# DAC.net
KiCad netlist of a schematic drawn in Altium Designer
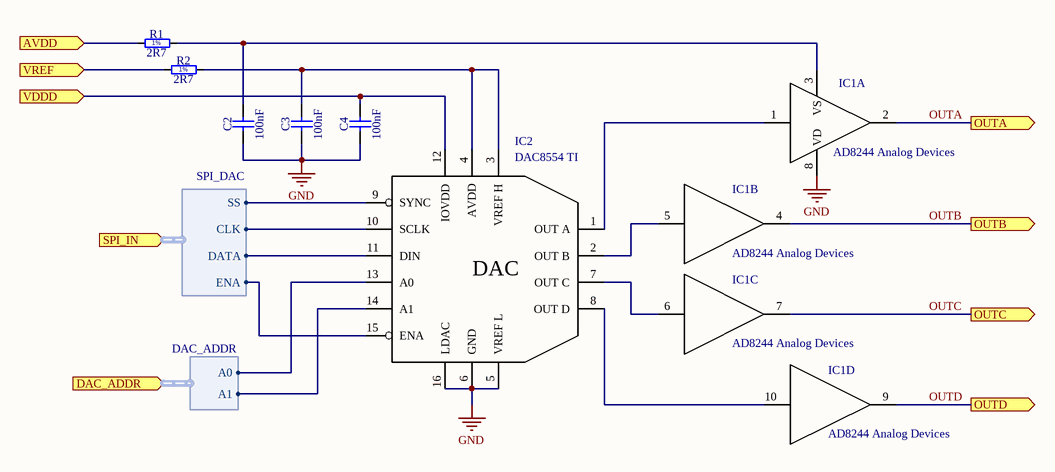
[diagram p0: DAC.SchDoc]

(export (version "E")
  (design (tool "Eeschema 10.0.6"))
  (components
    (comp (ref "C2")
      (value "100nF")
      (footprint "CAPC2012X135N")
      (description "Non-polarised capacitor")
      (fields
        (field (name "PART NUMBER") "CC0805_100NF_50V_10%_X7R")
        (field (name "VOLTAGE") "50V")
        (field (name "AUTHOR") "CERN DEM JLC")
      )
      (libsource (lib "Capacitors") (part "Capacitor - non polarized"))
    )
    (comp (ref "C3")
      (value "100nF")
      (footprint "CAPC2012X135N")
      (description "Non-polarised capacitor")
      (fields
        (field (name "PART NUMBER") "CC0805_100NF_50V_10%_X7R")
        (field (name "VOLTAGE") "50V")
        (field (name "AUTHOR") "CERN DEM JLC")
      )
      (libsource (lib "Capacitors") (part "Capacitor - non polarized"))
    )
    (comp (ref "C4")
      (value "100nF")
      (footprint "CAPC2012X135N")
      (description "Non-polarised capacitor")
      (fields
        (field (name "PART NUMBER") "CC0805_100NF_50V_10%_X7R")
        (field (name "VOLTAGE") "50V")
        (field (name "AUTHOR") "CERN DEM JLC")
      )
      (libsource (lib "Capacitors") (part "Capacitor - non polarized"))
    )
    (comp (ref "IC1")
      (value "AD8244 Analog Devices")
      (footprint "TSSOP50P490X110-10N")
      (fields (field (name "MANUFACTURER") "Analog Devices"))
      (libsource (lib "Additional") (part "AD8244"))
    )
    (comp (ref "IC2")
      (value "DAC8554 TI")
      (footprint "TSOP65P640X120-16N")
      (fields (field (name "MANUFACTURER") "TI"))
      (libsource (lib "Additional") (part "DAC8554"))
    )
    (comp (ref "R1")
      (value "2R7")
      (footprint "RESC2012X60N")
      (description "Resistor - 1%")
      (fields
        (field (name "PART NUMBER") "R0805_2R7_1%_0.125W_200PPM")
        (field (name "POWER") "0.125W")
        (field (name "AUTHOR") "CERN DEM JLC")
      )
      (libsource (lib "Resistors") (part "Resistor - 1%"))
    )
    (comp (ref "R2")
      (value "2R7")
      (footprint "RESC2012X60N")
      (description "Resistor - 1%")
      (fields
        (field (name "PART NUMBER") "R0805_2R7_1%_0.125W_200PPM")
        (field (name "POWER") "0.125W")
        (field (name "AUTHOR") "CERN DEM JLC")
      )
      (libsource (lib "Resistors") (part "Resistor - 1%"))
    )
  )
  (nets
    (net (code "3") (name "/A0") (class "Default")
      (node (ref "IC2") (pin "13") (pinfunction "A0_13") (pintype "passive"))
    )
    (net (code "4") (name "/A1") (class "Default")
      (node (ref "IC2") (pin "14") (pinfunction "A1_14") (pintype "passive"))
    )
    (net (code "5") (name "/AVDD") (class "Default")
      (node (ref "R1") (pin "1") (pinfunction "1_1") (pintype "passive"))
    )
    (net (code "6") (name "/CLK") (class "Default")
      (node (ref "IC2") (pin "10") (pinfunction "SCLK_10") (pintype "passive"))
    )
    (net (code "7") (name "/DATA") (class "Default")
      (node (ref "IC2") (pin "11") (pinfunction "DIN_11") (pintype "passive"))
    )
    (net (code "8") (name "/ENA") (class "Default")
      (node (ref "IC2") (pin "15") (pinfunction "ENA_15") (pintype "passive"))
    )
    (net (code "9") (name "/OUTA") (class "Default")
      (node (ref "IC1") (pin "2") (pinfunction "OUT_A_2") (pintype "passive"))
    )
    (net (code "10") (name "/OUTB") (class "Default")
      (node (ref "IC1") (pin "4") (pinfunction "OUT_B_4") (pintype "passive"))
    )
    (net (code "11") (name "/OUTC") (class "Default")
      (node (ref "IC1") (pin "7") (pinfunction "OUT_C_7") (pintype "passive"))
    )
    (net (code "12") (name "/OUTD") (class "Default")
      (node (ref "IC1") (pin "9") (pinfunction "OUT_D_9") (pintype "passive"))
    )
    (net (code "13") (name "/SS") (class "Default")
      (node (ref "IC2") (pin "9") (pinfunction "SYNC_9") (pintype "passive"))
    )
    (net (code "14") (name "/VDDD") (class "Default")
      (node (ref "C4") (pin "2") (pinfunction "2_2") (pintype "passive"))
      (node (ref "IC2") (pin "12") (pinfunction "IOVDD_12") (pintype "passive"))
    )
    (net (code "15") (name "/VREF") (class "Default")
      (node (ref "R2") (pin "1") (pinfunction "1_1") (pintype "passive"))
    )
    (net (code "18") (name "GND") (class "Default")
      (node (ref "C2") (pin "1") (pinfunction "1_1") (pintype "passive"))
      (node (ref "C3") (pin "1") (pinfunction "1_1") (pintype "passive"))
      (node (ref "C4") (pin "1") (pinfunction "1_1") (pintype "passive"))
      (node (ref "IC1") (pin "8") (pinfunction "VD_8") (pintype "passive"))
      (node (ref "IC2") (pin "16") (pinfunction "LDAC_16") (pintype "passive"))
      (node (ref "IC2") (pin "5") (pinfunction "VREF_L_5") (pintype "passive"))
      (node (ref "IC2") (pin "6") (pinfunction "GND_6") (pintype "passive"))
    )
    (net (code "19") (name "Net-(IC1A-IN_A)") (class "Default")
      (node (ref "IC1") (pin "1") (pinfunction "IN_A_1") (pintype "passive"))
      (node (ref "IC2") (pin "1") (pinfunction "OUT_A_1") (pintype "passive"))
    )
    (net (code "20") (name "Net-(IC1A-VS)") (class "Default")
      (node (ref "C2") (pin "2") (pinfunction "2_2") (pintype "passive"))
      (node (ref "IC1") (pin "3") (pinfunction "VS_3") (pintype "passive"))
      (node (ref "R1") (pin "2") (pinfunction "2_2") (pintype "passive"))
    )
    (net (code "21") (name "Net-(IC1B-IN_B)") (class "Default")
      (node (ref "IC1") (pin "5") (pinfunction "IN_B_5") (pintype "passive"))
      (node (ref "IC2") (pin "2") (pinfunction "OUT_B_2") (pintype "passive"))
    )
    (net (code "22") (name "Net-(IC1C-IN_C)") (class "Default")
      (node (ref "IC1") (pin "6") (pinfunction "IN_C_6") (pintype "passive"))
      (node (ref "IC2") (pin "7") (pinfunction "OUT_C_7") (pintype "passive"))
    )
    (net (code "23") (name "Net-(IC1D-IN_D)") (class "Default")
      (node (ref "IC1") (pin "10") (pinfunction "IN_D_10") (pintype "passive"))
      (node (ref "IC2") (pin "8") (pinfunction "OUT_D_8") (pintype "passive"))
    )
    (net (code "24") (name "Net-(IC2-AVDD)") (class "Default")
      (node (ref "C3") (pin "2") (pinfunction "2_2") (pintype "passive"))
      (node (ref "IC2") (pin "3") (pinfunction "VREF_H_3") (pintype "passive"))
      (node (ref "IC2") (pin "4") (pinfunction "AVDD_4") (pintype "passive"))
      (node (ref "R2") (pin "2") (pinfunction "2_2") (pintype "passive"))
    )
  )
)
